# ISP.net
KiCad netlist of a schematic drawn in EAGLE
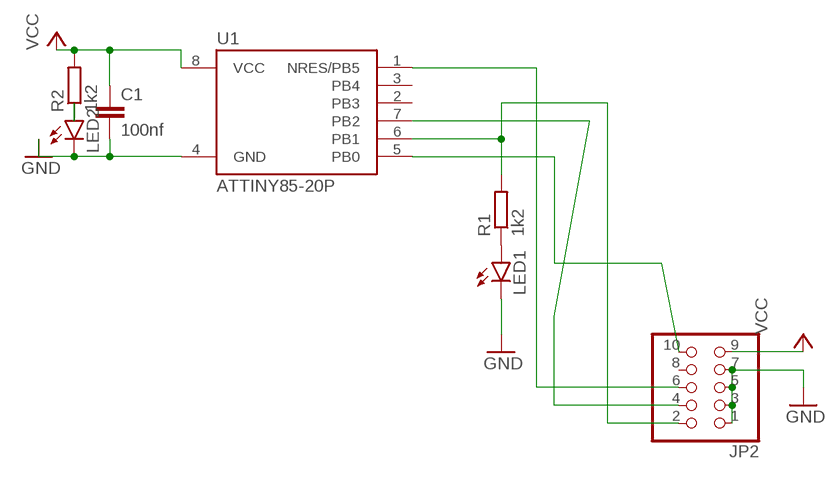
[diagram p0: schematic, sheet 1]

(export (version "E")
  (design (tool "Eeschema 10.0.6"))
  (components
    (comp (ref "C1")
      (value "100nf")
      (footprint "eagle-import:C5B2.5")
      (libsource (lib "eagle-import") (part "C5/2.5"))
    )
    (comp (ref "JP2")
      (value "PINHD-2X5")
      (footprint "eagle-import:2X05")
      (libsource (lib "eagle-import") (part "PINHD-2X5"))
    )
    (comp (ref "LED1")
      (value "LED5MM")
      (footprint "eagle-import:LED5MM")
      (libsource (lib "eagle-import") (part "LED5MM"))
    )
    (comp (ref "LED2")
      (value "LED5MM")
      (footprint "eagle-import:LED5MM")
      (libsource (lib "eagle-import") (part "LED5MM"))
    )
    (comp (ref "R1")
      (value "1k2")
      (footprint "eagle-import:0204_7")
      (libsource (lib "eagle-import") (part "R-EU_0204/7"))
    )
    (comp (ref "R2")
      (value "1k2")
      (footprint "eagle-import:0204_7")
      (libsource (lib "eagle-import") (part "R-EU_0204/7"))
    )
    (comp (ref "U1")
      (value "ATTINY85-20P")
      (footprint "eagle-import:PDIP08_300MIL")
      (libsource (lib "eagle-import") (part "ATTINY85P-20"))
    )
  )
  (nets
    (net (code "1") (name "GND") (class "Default")
      (node (ref "C1") (pin "2") (pinfunction "2_2") (pintype "passive"))
      (node (ref "JP2") (pin "1") (pinfunction "1_1") (pintype "passive"))
      (node (ref "JP2") (pin "3") (pinfunction "3_3") (pintype "passive"))
      (node (ref "JP2") (pin "5") (pinfunction "5_5") (pintype "passive"))
      (node (ref "JP2") (pin "7") (pinfunction "7_7") (pintype "passive"))
      (node (ref "LED1") (pin "K") (pinfunction "C_K") (pintype "passive"))
      (node (ref "LED2") (pin "K") (pinfunction "C_K") (pintype "passive"))
      (node (ref "U1") (pin "4") (pinfunction "GND_4") (pintype "power_in"))
    )
    (net (code "2") (name "Net-(LED1-PadA)") (class "Default")
      (node (ref "LED1") (pin "A") (pinfunction "A_A") (pintype "passive"))
      (node (ref "R1") (pin "1") (pinfunction "1_1") (pintype "passive"))
    )
    (net (code "3") (name "Net-(LED2-PadA)") (class "Default")
      (node (ref "LED2") (pin "A") (pinfunction "A_A") (pintype "passive"))
      (node (ref "R2") (pin "1") (pinfunction "1_1") (pintype "passive"))
    )
    (net (code "4") (name "Net-(U1-NRES{slash}PB5)") (class "Default")
      (node (ref "JP2") (pin "6") (pinfunction "6_6") (pintype "passive"))
      (node (ref "U1") (pin "1") (pinfunction "NRES/PB5_1") (pintype "bidirectional"))
    )
    (net (code "5") (name "Net-(U1-PB0)") (class "Default")
      (node (ref "JP2") (pin "10") (pinfunction "10_10") (pintype "passive"))
      (node (ref "U1") (pin "5") (pinfunction "PB0_5") (pintype "bidirectional"))
    )
    (net (code "6") (name "Net-(U1-PB1)") (class "Default")
      (node (ref "JP2") (pin "2") (pinfunction "2_2") (pintype "passive"))
      (node (ref "R1") (pin "2") (pinfunction "2_2") (pintype "passive"))
      (node (ref "U1") (pin "6") (pinfunction "PB1_6") (pintype "bidirectional"))
    )
    (net (code "7") (name "Net-(U1-PB2)") (class "Default")
      (node (ref "JP2") (pin "4") (pinfunction "4_4") (pintype "passive"))
      (node (ref "U1") (pin "7") (pinfunction "PB2_7") (pintype "bidirectional"))
    )
    (net (code "8") (name "VCC") (class "Default")
      (node (ref "C1") (pin "1") (pinfunction "1_1") (pintype "passive"))
      (node (ref "JP2") (pin "9") (pinfunction "9_9") (pintype "passive"))
      (node (ref "R2") (pin "2") (pinfunction "2_2") (pintype "passive"))
      (node (ref "U1") (pin "8") (pinfunction "VCC_8") (pintype "power_in"))
    )
    (net (code "9") (name "unconnected-(JP2-Pad8)") (class "Default")
      (node (ref "JP2") (pin "8") (pinfunction "8_8") (pintype "passive"))
    )
    (net (code "10") (name "unconnected-(U1-PB3-Pad2)") (class "Default")
      (node (ref "U1") (pin "2") (pinfunction "PB3_2") (pintype "bidirectional"))
    )
    (net (code "11") (name "unconnected-(U1-PB4-Pad3)") (class "Default")
      (node (ref "U1") (pin "3") (pinfunction "PB4_3") (pintype "bidirectional"))
    )
  )
)
